# PC1_Codec.net
KiCad netlist of a schematic drawn in Altium Designer
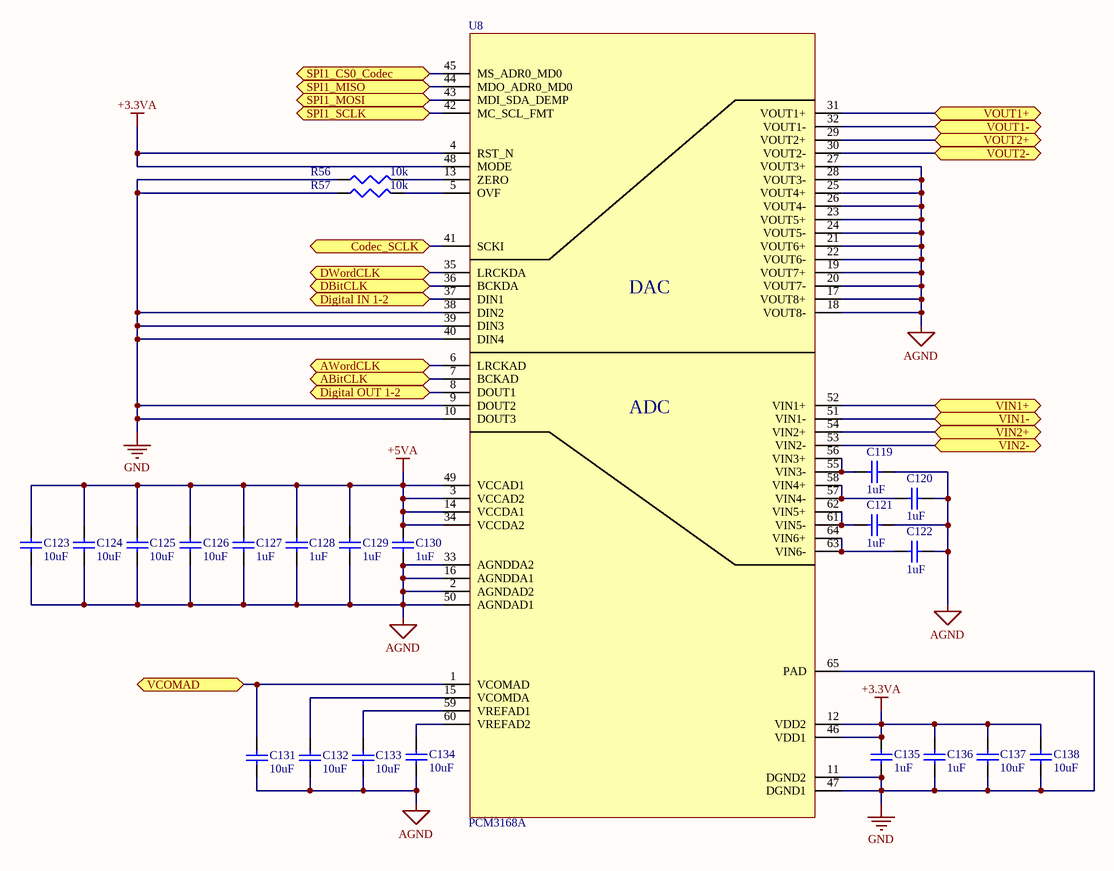
[diagram p0: PC1_Codec.SchDoc]

(export (version "E")
  (design (tool "Eeschema 10.0.6"))
  (components
    (comp (ref "C119")
      (value "1uF")
      (footprint "CAPC1608X08")
      (description "Capacitor")
      (libsource (lib "Michel") (part "Cap Semi"))
    )
    (comp (ref "C120")
      (value "1uF")
      (footprint "CAPC1608X08")
      (description "Capacitor")
      (libsource (lib "Michel") (part "Cap Semi"))
    )
    (comp (ref "C121")
      (value "1uF")
      (footprint "CAPC1608X08")
      (description "Capacitor")
      (libsource (lib "Michel") (part "Cap Semi"))
    )
    (comp (ref "C122")
      (value "1uF")
      (footprint "CAPC1608X08")
      (description "Capacitor")
      (libsource (lib "Michel") (part "Cap Semi"))
    )
    (comp (ref "C123")
      (value "10uF")
      (footprint "CAPC1608X08")
      (description "Capacitor (Semiconductor SIM Model)")
      (libsource (lib "Michel") (part "Cap Semi"))
    )
    (comp (ref "C124")
      (value "10uF")
      (footprint "CAPC1608X08")
      (description "Capacitor (Semiconductor SIM Model)")
      (libsource (lib "Michel") (part "Cap Semi"))
    )
    (comp (ref "C125")
      (value "10uF")
      (footprint "CAPC1608X08")
      (description "Capacitor (Semiconductor SIM Model)")
      (libsource (lib "Michel") (part "Cap Semi"))
    )
    (comp (ref "C126")
      (value "10uF")
      (footprint "CAPC1608X08")
      (description "Capacitor (Semiconductor SIM Model)")
      (libsource (lib "Michel") (part "Cap Semi"))
    )
    (comp (ref "C127")
      (value "1uF")
      (footprint "CAPC1608X08")
      (description "Capacitor")
      (libsource (lib "Michel") (part "Cap Semi"))
    )
    (comp (ref "C128")
      (value "1uF")
      (footprint "CAPC1608X08")
      (description "Capacitor")
      (libsource (lib "Michel") (part "Cap Semi"))
    )
    (comp (ref "C129")
      (value "1uF")
      (footprint "CAPC1608X08")
      (description "Capacitor")
      (libsource (lib "Michel") (part "Cap Semi"))
    )
    (comp (ref "C130")
      (value "1uF")
      (footprint "CAPC1608X08")
      (description "Capacitor")
      (libsource (lib "Michel") (part "Cap Semi"))
    )
    (comp (ref "C131")
      (value "10uF")
      (footprint "CAPC1608X08")
      (description "Capacitor (Semiconductor SIM Model)")
      (libsource (lib "Michel") (part "Cap Semi"))
    )
    (comp (ref "C132")
      (value "10uF")
      (footprint "CAPC1608X08")
      (description "Capacitor (Semiconductor SIM Model)")
      (libsource (lib "Michel") (part "Cap Semi"))
    )
    (comp (ref "C133")
      (value "10uF")
      (footprint "CAPC1608X08")
      (description "Capacitor (Semiconductor SIM Model)")
      (libsource (lib "Michel") (part "Cap Semi"))
    )
    (comp (ref "C134")
      (value "10uF")
      (footprint "CAPC1608X08")
      (description "Capacitor (Semiconductor SIM Model)")
      (libsource (lib "Michel") (part "Cap Semi"))
    )
    (comp (ref "C135")
      (value "1uF")
      (footprint "CAPC1608X08")
      (description "Capacitor")
      (libsource (lib "Michel") (part "Cap Semi"))
    )
    (comp (ref "C136")
      (value "1uF")
      (footprint "CAPC1608X08")
      (description "Capacitor")
      (libsource (lib "Michel") (part "Cap Semi"))
    )
    (comp (ref "C137")
      (value "10uF")
      (footprint "CAPC1608X08")
      (description "Capacitor (Semiconductor SIM Model)")
      (libsource (lib "Michel") (part "Cap Semi"))
    )
    (comp (ref "C138")
      (value "10uF")
      (footprint "CAPC1608X08")
      (description "Capacitor (Semiconductor SIM Model)")
      (libsource (lib "Michel") (part "Cap Semi"))
    )
    (comp (ref "R56")
      (value "10k")
      (footprint "RESC1608X05")
      (description "Resistor")
      (fields (field (name "Comment") "Res3"))
      (libsource (lib "Michel") (part "Res3"))
    )
    (comp (ref "R57")
      (value "10k")
      (footprint "RESC1608X05")
      (description "Resistor")
      (fields (field (name "Comment") "Res3"))
      (libsource (lib "Michel") (part "Res3"))
    )
    (comp (ref "U8")
      (value "PCM3168A")
      (footprint "PAP64_7X7P26-M")
      (description "Codec Audio, 6ADC/8DAC")
      (libsource (lib "Michel") (part "PCM3168APAPR"))
    )
  )
  (nets
    (net (code "1") (name "+3.3VA") (class "Default")
      (node (ref "C135") (pin "2") (pinfunction "2_2") (pintype "passive"))
      (node (ref "C136") (pin "2") (pinfunction "2_2") (pintype "passive"))
      (node (ref "C137") (pin "1") (pinfunction "1_1") (pintype "passive"))
      (node (ref "C138") (pin "1") (pinfunction "1_1") (pintype "passive"))
      (node (ref "U8") (pin "12") (pinfunction "VDD2_12") (pintype "passive"))
      (node (ref "U8") (pin "4") (pinfunction "RST_N_4") (pintype "passive"))
      (node (ref "U8") (pin "46") (pinfunction "VDD1_46") (pintype "passive"))
      (node (ref "U8") (pin "48") (pinfunction "MODE_48") (pintype "passive"))
    )
    (net (code "2") (name "+5VA") (class "Default")
      (node (ref "C123") (pin "1") (pinfunction "1_1") (pintype "passive"))
      (node (ref "C124") (pin "1") (pinfunction "1_1") (pintype "passive"))
      (node (ref "C125") (pin "1") (pinfunction "1_1") (pintype "passive"))
      (node (ref "C126") (pin "1") (pinfunction "1_1") (pintype "passive"))
      (node (ref "C127") (pin "2") (pinfunction "2_2") (pintype "passive"))
      (node (ref "C128") (pin "2") (pinfunction "2_2") (pintype "passive"))
      (node (ref "C129") (pin "2") (pinfunction "2_2") (pintype "passive"))
      (node (ref "C130") (pin "2") (pinfunction "2_2") (pintype "passive"))
      (node (ref "U8") (pin "14") (pinfunction "VCCDA1_14") (pintype "passive"))
      (node (ref "U8") (pin "3") (pinfunction "VCCAD2_3") (pintype "passive"))
      (node (ref "U8") (pin "34") (pinfunction "VCCDA2_34") (pintype "passive"))
      (node (ref "U8") (pin "49") (pinfunction "VCCAD1_49") (pintype "passive"))
    )
    (net (code "3") (name "/ABitCLK") (class "Default")
      (node (ref "U8") (pin "7") (pinfunction "BCKAD_7") (pintype "passive"))
    )
    (net (code "4") (name "/AWordCLK") (class "Default")
      (node (ref "U8") (pin "6") (pinfunction "LRCKAD_6") (pintype "passive"))
    )
    (net (code "5") (name "/Codec_SCLK") (class "Default")
      (node (ref "U8") (pin "41") (pinfunction "SCKI_41") (pintype "passive"))
    )
    (net (code "6") (name "/DBitCLK") (class "Default")
      (node (ref "U8") (pin "36") (pinfunction "BCKDA_36") (pintype "passive"))
    )
    (net (code "7") (name "/DWordCLK") (class "Default")
      (node (ref "U8") (pin "35") (pinfunction "LRCKDA_35") (pintype "passive"))
    )
    (net (code "8") (name "/Digital IN 1-2") (class "Default")
      (node (ref "U8") (pin "37") (pinfunction "DIN1_37") (pintype "passive"))
    )
    (net (code "9") (name "/Digital OUT 1-2") (class "Default")
      (node (ref "U8") (pin "8") (pinfunction "DOUT1_8") (pintype "passive"))
    )
    (net (code "10") (name "/SPI1_CS0_Codec") (class "Default")
      (node (ref "U8") (pin "45") (pinfunction "MS_ADR0_MD0_45") (pintype "passive"))
    )
    (net (code "11") (name "/SPI1_MISO") (class "Default")
      (node (ref "U8") (pin "44") (pinfunction "MDO_ADR0_MD0_44") (pintype "passive"))
    )
    (net (code "12") (name "/SPI1_MOSI") (class "Default")
      (node (ref "U8") (pin "43") (pinfunction "MDI_SDA_DEMP_43") (pintype "passive"))
    )
    (net (code "13") (name "/SPI1_SCLK") (class "Default")
      (node (ref "U8") (pin "42") (pinfunction "MC_SCL_FMT_42") (pintype "passive"))
    )
    (net (code "14") (name "/VCOMAD") (class "Default")
      (node (ref "U8") (pin "1") (pinfunction "VCOMAD_1") (pintype "passive"))
    )
    (net (code "15") (name "/VIN1+") (class "Default")
      (node (ref "U8") (pin "52") (pinfunction "VIN1+_52") (pintype "passive"))
    )
    (net (code "16") (name "/VIN1-") (class "Default")
      (node (ref "U8") (pin "51") (pinfunction "VIN1-_51") (pintype "passive"))
    )
    (net (code "17") (name "/VIN2+") (class "Default")
      (node (ref "U8") (pin "54") (pinfunction "VIN2+_54") (pintype "passive"))
    )
    (net (code "18") (name "/VIN2-") (class "Default")
      (node (ref "U8") (pin "53") (pinfunction "VIN2-_53") (pintype "passive"))
    )
    (net (code "19") (name "/VOUT1+") (class "Default")
      (node (ref "U8") (pin "31") (pinfunction "VOUT1+_31") (pintype "passive"))
    )
    (net (code "20") (name "/VOUT1-") (class "Default")
      (node (ref "U8") (pin "32") (pinfunction "VOUT1-_32") (pintype "passive"))
    )
    (net (code "21") (name "/VOUT2+") (class "Default")
      (node (ref "U8") (pin "29") (pinfunction "VOUT2+_29") (pintype "passive"))
    )
    (net (code "22") (name "/VOUT2-") (class "Default")
      (node (ref "U8") (pin "30") (pinfunction "VOUT2-_30") (pintype "passive"))
    )
    (net (code "23") (name "AGND") (class "Default")
      (node (ref "C119") (pin "1") (pinfunction "1_1") (pintype "passive"))
      (node (ref "C120") (pin "1") (pinfunction "1_1") (pintype "passive"))
      (node (ref "C121") (pin "1") (pinfunction "1_1") (pintype "passive"))
      (node (ref "C122") (pin "1") (pinfunction "1_1") (pintype "passive"))
      (node (ref "C123") (pin "2") (pinfunction "2_2") (pintype "passive"))
      (node (ref "C124") (pin "2") (pinfunction "2_2") (pintype "passive"))
      (node (ref "C125") (pin "2") (pinfunction "2_2") (pintype "passive"))
      (node (ref "C126") (pin "2") (pinfunction "2_2") (pintype "passive"))
      (node (ref "C127") (pin "1") (pinfunction "1_1") (pintype "passive"))
      (node (ref "C128") (pin "1") (pinfunction "1_1") (pintype "passive"))
      (node (ref "C129") (pin "1") (pinfunction "1_1") (pintype "passive"))
      (node (ref "C130") (pin "1") (pinfunction "1_1") (pintype "passive"))
      (node (ref "C131") (pin "2") (pinfunction "2_2") (pintype "passive"))
      (node (ref "C132") (pin "2") (pinfunction "2_2") (pintype "passive"))
      (node (ref "C133") (pin "2") (pinfunction "2_2") (pintype "passive"))
      (node (ref "C134") (pin "2") (pinfunction "2_2") (pintype "passive"))
      (node (ref "U8") (pin "16") (pinfunction "AGNDDA1_16") (pintype "passive"))
      (node (ref "U8") (pin "17") (pinfunction "VOUT8+_17") (pintype "passive"))
      (node (ref "U8") (pin "18") (pinfunction "VOUT8-_18") (pintype "passive"))
      (node (ref "U8") (pin "19") (pinfunction "VOUT7+_19") (pintype "passive"))
      (node (ref "U8") (pin "2") (pinfunction "AGNDAD2_2") (pintype "passive"))
      (node (ref "U8") (pin "20") (pinfunction "VOUT7-_20") (pintype "passive"))
      (node (ref "U8") (pin "21") (pinfunction "VOUT6+_21") (pintype "passive"))
      (node (ref "U8") (pin "22") (pinfunction "VOUT6-_22") (pintype "passive"))
      (node (ref "U8") (pin "23") (pinfunction "VOUT5+_23") (pintype "passive"))
      (node (ref "U8") (pin "24") (pinfunction "VOUT5-_24") (pintype "passive"))
      (node (ref "U8") (pin "25") (pinfunction "VOUT4+_25") (pintype "passive"))
      (node (ref "U8") (pin "26") (pinfunction "VOUT4-_26") (pintype "passive"))
      (node (ref "U8") (pin "27") (pinfunction "VOUT3+_27") (pintype "passive"))
      (node (ref "U8") (pin "28") (pinfunction "VOUT3-_28") (pintype "passive"))
      (node (ref "U8") (pin "33") (pinfunction "AGNDDA2_33") (pintype "passive"))
      (node (ref "U8") (pin "50") (pinfunction "AGNDAD1_50") (pintype "passive"))
    )
    (net (code "24") (name "GND") (class "Default")
      (node (ref "C135") (pin "1") (pinfunction "1_1") (pintype "passive"))
      (node (ref "C136") (pin "1") (pinfunction "1_1") (pintype "passive"))
      (node (ref "C137") (pin "2") (pinfunction "2_2") (pintype "passive"))
      (node (ref "C138") (pin "2") (pinfunction "2_2") (pintype "passive"))
      (node (ref "R56") (pin "1") (pinfunction "1_1") (pintype "passive"))
      (node (ref "R57") (pin "1") (pinfunction "1_1") (pintype "passive"))
      (node (ref "U8") (pin "10") (pinfunction "DOUT3_10") (pintype "passive"))
      (node (ref "U8") (pin "11") (pinfunction "DGND2_11") (pintype "passive"))
      (node (ref "U8") (pin "38") (pinfunction "DIN2_38") (pintype "passive"))
      (node (ref "U8") (pin "39") (pinfunction "DIN3_39") (pintype "passive"))
      (node (ref "U8") (pin "40") (pinfunction "DIN4_40") (pintype "passive"))
      (node (ref "U8") (pin "47") (pinfunction "DGND1_47") (pintype "passive"))
      (node (ref "U8") (pin "65") (pinfunction "PAD_65") (pintype "passive"))
      (node (ref "U8") (pin "9") (pinfunction "DOUT2_9") (pintype "passive"))
    )
    (net (code "25") (name "Net-(U8-OVF)") (class "Default")
      (node (ref "R57") (pin "2") (pinfunction "2_2") (pintype "passive"))
      (node (ref "U8") (pin "5") (pinfunction "OVF_5") (pintype "passive"))
    )
    (net (code "26") (name "Net-(U8-VCOMDA)") (class "Default")
      (node (ref "C132") (pin "1") (pinfunction "1_1") (pintype "passive"))
      (node (ref "U8") (pin "15") (pinfunction "VCOMDA_15") (pintype "passive"))
    )
    (net (code "27") (name "Net-(U8-VIN3+)") (class "Default")
      (node (ref "C119") (pin "2") (pinfunction "2_2") (pintype "passive"))
      (node (ref "U8") (pin "55") (pinfunction "VIN3-_55") (pintype "passive"))
      (node (ref "U8") (pin "56") (pinfunction "VIN3+_56") (pintype "passive"))
    )
    (net (code "28") (name "Net-(U8-VIN4+)") (class "Default")
      (node (ref "C120") (pin "2") (pinfunction "2_2") (pintype "passive"))
      (node (ref "U8") (pin "57") (pinfunction "VIN4-_57") (pintype "passive"))
      (node (ref "U8") (pin "58") (pinfunction "VIN4+_58") (pintype "passive"))
    )
    (net (code "29") (name "Net-(U8-VIN5+)") (class "Default")
      (node (ref "C121") (pin "2") (pinfunction "2_2") (pintype "passive"))
      (node (ref "U8") (pin "61") (pinfunction "VIN5-_61") (pintype "passive"))
      (node (ref "U8") (pin "62") (pinfunction "VIN5+_62") (pintype "passive"))
    )
    (net (code "30") (name "Net-(U8-VIN6+)") (class "Default")
      (node (ref "C122") (pin "2") (pinfunction "2_2") (pintype "passive"))
      (node (ref "U8") (pin "63") (pinfunction "VIN6-_63") (pintype "passive"))
      (node (ref "U8") (pin "64") (pinfunction "VIN6+_64") (pintype "passive"))
    )
    (net (code "31") (name "Net-(U8-VREFAD1)") (class "Default")
      (node (ref "C133") (pin "1") (pinfunction "1_1") (pintype "passive"))
      (node (ref "U8") (pin "59") (pinfunction "VREFAD1_59") (pintype "passive"))
    )
    (net (code "32") (name "Net-(U8-VREFAD2)") (class "Default")
      (node (ref "C134") (pin "1") (pinfunction "1_1") (pintype "passive"))
      (node (ref "U8") (pin "60") (pinfunction "VREFAD2_60") (pintype "passive"))
    )
    (net (code "33") (name "Net-(U8-ZERO)") (class "Default")
      (node (ref "R56") (pin "2") (pinfunction "2_2") (pintype "passive"))
      (node (ref "U8") (pin "13") (pinfunction "ZERO_13") (pintype "passive"))
    )
    (net (code "34") (name "unconnected-(C131-Pad1)") (class "Default")
      (node (ref "C131") (pin "1") (pinfunction "1_1") (pintype "passive"))
    )
  )
)
